# inversor.net
KiCad netlist of a schematic drawn in EAGLE
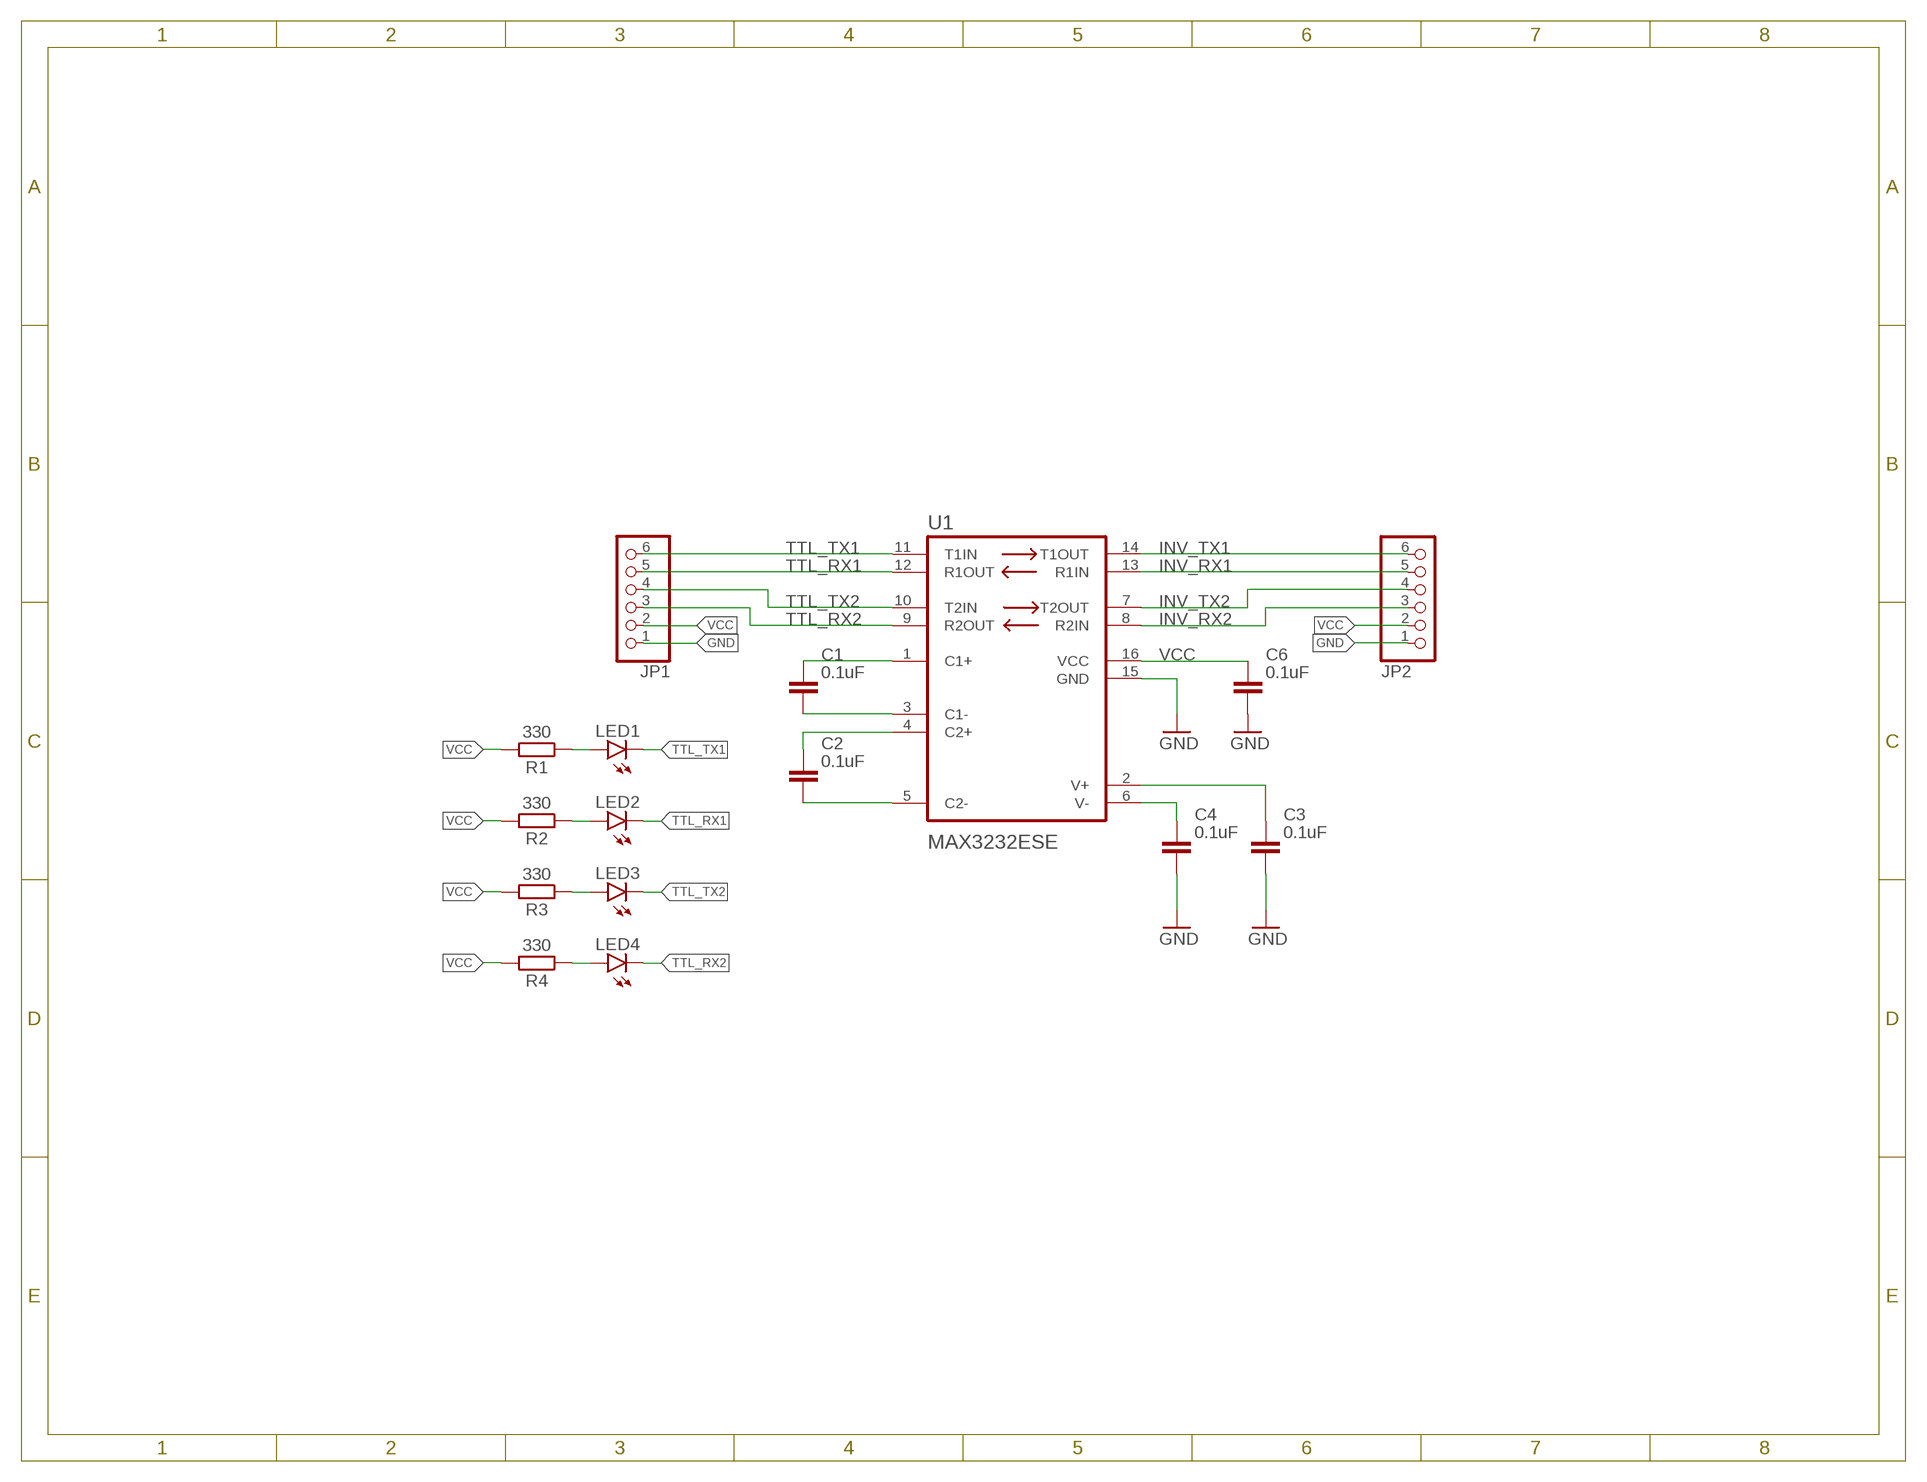
[diagram p0: schematic, sheet 1]

(export (version "E")
  (design (tool "Eeschema 10.0.6"))
  (components
    (comp (ref "C1")
      (value "0.1uF")
      (footprint "eagle-import:CAPC1608X85")
      (libsource (lib "eagle-import") (part "CCHIP-0603(1608-METRIC)_"))
    )
    (comp (ref "C2")
      (value "0.1uF")
      (footprint "eagle-import:CAPC1608X85")
      (libsource (lib "eagle-import") (part "CCHIP-0603(1608-METRIC)_"))
    )
    (comp (ref "C3")
      (value "0.1uF")
      (footprint "eagle-import:CAPC1608X85")
      (libsource (lib "eagle-import") (part "CCHIP-0603(1608-METRIC)_"))
    )
    (comp (ref "C4")
      (value "0.1uF")
      (footprint "eagle-import:CAPC1608X85")
      (libsource (lib "eagle-import") (part "CCHIP-0603(1608-METRIC)_"))
    )
    (comp (ref "C6")
      (value "0.1uF")
      (footprint "eagle-import:CAPC1608X85")
      (libsource (lib "eagle-import") (part "CCHIP-0603(1608-METRIC)_"))
    )
    (comp (ref "JP1")
      (value "PINHD-1X6")
      (footprint "eagle-import:1X06")
      (libsource (lib "eagle-import") (part "PINHD-1X6"))
    )
    (comp (ref "JP2")
      (value "PINHD-1X6")
      (footprint "eagle-import:1X06")
      (libsource (lib "eagle-import") (part "PINHD-1X6"))
    )
    (comp (ref "LED1")
      (value "LED")
      (footprint "eagle-import:CHIPLED_0805")
      (fields (field (name "MF") "baizou") (field (name "MP") "BZ-C0805-B3-E1"))
      (libsource (lib "eagle-import") (part "LEDCHIPLED_0805"))
    )
    (comp (ref "LED2")
      (value "LED")
      (footprint "eagle-import:CHIPLED_0805")
      (fields (field (name "MF") "baizou") (field (name "MP") "BZ-C0805-B3-E1"))
      (libsource (lib "eagle-import") (part "LEDCHIPLED_0805"))
    )
    (comp (ref "LED3")
      (value "LED")
      (footprint "eagle-import:CHIPLED_0805")
      (fields (field (name "MF") "baizou") (field (name "MP") "BZ-C0805-B3-E1"))
      (libsource (lib "eagle-import") (part "LEDCHIPLED_0805"))
    )
    (comp (ref "LED4")
      (value "LED")
      (footprint "eagle-import:CHIPLED_0805")
      (fields (field (name "MF") "baizou") (field (name "MP") "BZ-C0805-B3-E1"))
      (libsource (lib "eagle-import") (part "LEDCHIPLED_0805"))
    )
    (comp (ref "R1")
      (value "330")
      (footprint "eagle-import:RESC1608X60")
      (libsource (lib "eagle-import") (part "RCHIP-0603(1608-METRIC)_"))
    )
    (comp (ref "R2")
      (value "330")
      (footprint "eagle-import:RESC1608X60")
      (libsource (lib "eagle-import") (part "RCHIP-0603(1608-METRIC)_"))
    )
    (comp (ref "R3")
      (value "330")
      (footprint "eagle-import:RESC1608X60")
      (libsource (lib "eagle-import") (part "RCHIP-0603(1608-METRIC)_"))
    )
    (comp (ref "R4")
      (value "330")
      (footprint "eagle-import:RESC1608X60")
      (libsource (lib "eagle-import") (part "RCHIP-0603(1608-METRIC)_"))
    )
    (comp (ref "U1")
      (value "MAX3232ESE")
      (footprint "eagle-import:SOIC127P600X175-16N")
      (fields
        (field (name "MF") "Maxim Integrated")
        (field (name "MP") "MAX3232ESE+T")
        (field (name "PACKAGE") "SOIC-16_3.9x9.9x1.27P")
      )
      (libsource (lib "eagle-import") (part "MAX3232ESE"))
    )
  )
  (nets
    (net (code "1") (name "/INV_RX1") (class "Default")
      (node (ref "JP2") (pin "5") (pinfunction "5_5") (pintype "passive"))
      (node (ref "U1") (pin "13") (pinfunction "R1IN_13") (pintype "input"))
    )
    (net (code "2") (name "/INV_RX2") (class "Default")
      (node (ref "JP2") (pin "3") (pinfunction "3_3") (pintype "passive"))
      (node (ref "U1") (pin "8") (pinfunction "R2IN_8") (pintype "input"))
    )
    (net (code "3") (name "/INV_TX1") (class "Default")
      (node (ref "JP2") (pin "6") (pinfunction "6_6") (pintype "passive"))
      (node (ref "U1") (pin "14") (pinfunction "T1OUT_14") (pintype "output"))
    )
    (net (code "4") (name "/INV_TX2") (class "Default")
      (node (ref "JP2") (pin "4") (pinfunction "4_4") (pintype "passive"))
      (node (ref "U1") (pin "7") (pinfunction "T2OUT_7") (pintype "output"))
    )
    (net (code "5") (name "GND") (class "Default")
      (node (ref "C3") (pin "2") (pinfunction "2_2") (pintype "passive"))
      (node (ref "C4") (pin "2") (pinfunction "2_2") (pintype "passive"))
      (node (ref "C6") (pin "2") (pinfunction "2_2") (pintype "passive"))
      (node (ref "JP1") (pin "1") (pinfunction "1_1") (pintype "passive"))
      (node (ref "JP2") (pin "1") (pinfunction "1_1") (pintype "passive"))
      (node (ref "U1") (pin "15") (pinfunction "GND_15") (pintype "power_in"))
    )
    (net (code "6") (name "Net-(LED1-PadA)") (class "Default")
      (node (ref "LED1") (pin "A") (pinfunction "A_A") (pintype "passive"))
      (node (ref "R1") (pin "1") (pinfunction "1_1") (pintype "passive"))
    )
    (net (code "7") (name "Net-(LED2-PadA)") (class "Default")
      (node (ref "LED2") (pin "A") (pinfunction "A_A") (pintype "passive"))
      (node (ref "R2") (pin "1") (pinfunction "1_1") (pintype "passive"))
    )
    (net (code "8") (name "Net-(LED3-PadA)") (class "Default")
      (node (ref "LED3") (pin "A") (pinfunction "A_A") (pintype "passive"))
      (node (ref "R3") (pin "1") (pinfunction "1_1") (pintype "passive"))
    )
    (net (code "9") (name "Net-(LED4-PadA)") (class "Default")
      (node (ref "LED4") (pin "A") (pinfunction "A_A") (pintype "passive"))
      (node (ref "R4") (pin "1") (pinfunction "1_1") (pintype "passive"))
    )
    (net (code "10") (name "Net-(U1-C1+)") (class "Default")
      (node (ref "C1") (pin "1") (pinfunction "1_1") (pintype "passive"))
      (node (ref "U1") (pin "1") (pinfunction "C1+_1") (pintype "bidirectional"))
    )
    (net (code "11") (name "Net-(U1-C1-)") (class "Default")
      (node (ref "C1") (pin "2") (pinfunction "2_2") (pintype "passive"))
      (node (ref "U1") (pin "3") (pinfunction "C1-_3") (pintype "bidirectional"))
    )
    (net (code "12") (name "Net-(U1-C2+)") (class "Default")
      (node (ref "C2") (pin "1") (pinfunction "1_1") (pintype "passive"))
      (node (ref "U1") (pin "4") (pinfunction "C2+_4") (pintype "bidirectional"))
    )
    (net (code "13") (name "Net-(U1-C2-)") (class "Default")
      (node (ref "C2") (pin "2") (pinfunction "2_2") (pintype "passive"))
      (node (ref "U1") (pin "5") (pinfunction "C2-_5") (pintype "bidirectional"))
    )
    (net (code "14") (name "Net-(U1-V+)") (class "Default")
      (node (ref "C3") (pin "1") (pinfunction "1_1") (pintype "passive"))
      (node (ref "U1") (pin "2") (pinfunction "V+_2") (pintype "power_in"))
    )
    (net (code "15") (name "Net-(U1-V-)") (class "Default")
      (node (ref "C4") (pin "1") (pinfunction "1_1") (pintype "passive"))
      (node (ref "U1") (pin "6") (pinfunction "V-_6") (pintype "power_in"))
    )
    (net (code "16") (name "TTL_RX1") (class "Default")
      (node (ref "JP1") (pin "5") (pinfunction "5_5") (pintype "passive"))
      (node (ref "LED2") (pin "C") (pinfunction "C_C") (pintype "passive"))
      (node (ref "U1") (pin "12") (pinfunction "R1OUT_12") (pintype "output"))
    )
    (net (code "17") (name "TTL_RX2") (class "Default")
      (node (ref "JP1") (pin "3") (pinfunction "3_3") (pintype "passive"))
      (node (ref "LED4") (pin "C") (pinfunction "C_C") (pintype "passive"))
      (node (ref "U1") (pin "9") (pinfunction "R2OUT_9") (pintype "output"))
    )
    (net (code "18") (name "TTL_TX1") (class "Default")
      (node (ref "JP1") (pin "6") (pinfunction "6_6") (pintype "passive"))
      (node (ref "LED1") (pin "C") (pinfunction "C_C") (pintype "passive"))
      (node (ref "U1") (pin "11") (pinfunction "T1IN_11") (pintype "input"))
    )
    (net (code "19") (name "TTL_TX2") (class "Default")
      (node (ref "JP1") (pin "4") (pinfunction "4_4") (pintype "passive"))
      (node (ref "LED3") (pin "C") (pinfunction "C_C") (pintype "passive"))
      (node (ref "U1") (pin "10") (pinfunction "T2IN_10") (pintype "input"))
    )
    (net (code "20") (name "VCC") (class "Default")
      (node (ref "C6") (pin "1") (pinfunction "1_1") (pintype "passive"))
      (node (ref "JP1") (pin "2") (pinfunction "2_2") (pintype "passive"))
      (node (ref "JP2") (pin "2") (pinfunction "2_2") (pintype "passive"))
      (node (ref "R1") (pin "2") (pinfunction "2_2") (pintype "passive"))
      (node (ref "R2") (pin "2") (pinfunction "2_2") (pintype "passive"))
      (node (ref "R3") (pin "2") (pinfunction "2_2") (pintype "passive"))
      (node (ref "R4") (pin "2") (pinfunction "2_2") (pintype "passive"))
      (node (ref "U1") (pin "16") (pinfunction "VCC_16") (pintype "power_in"))
    )
  )
)
